# USBCharger.net
KiCad netlist of a schematic drawn in Altium Designer
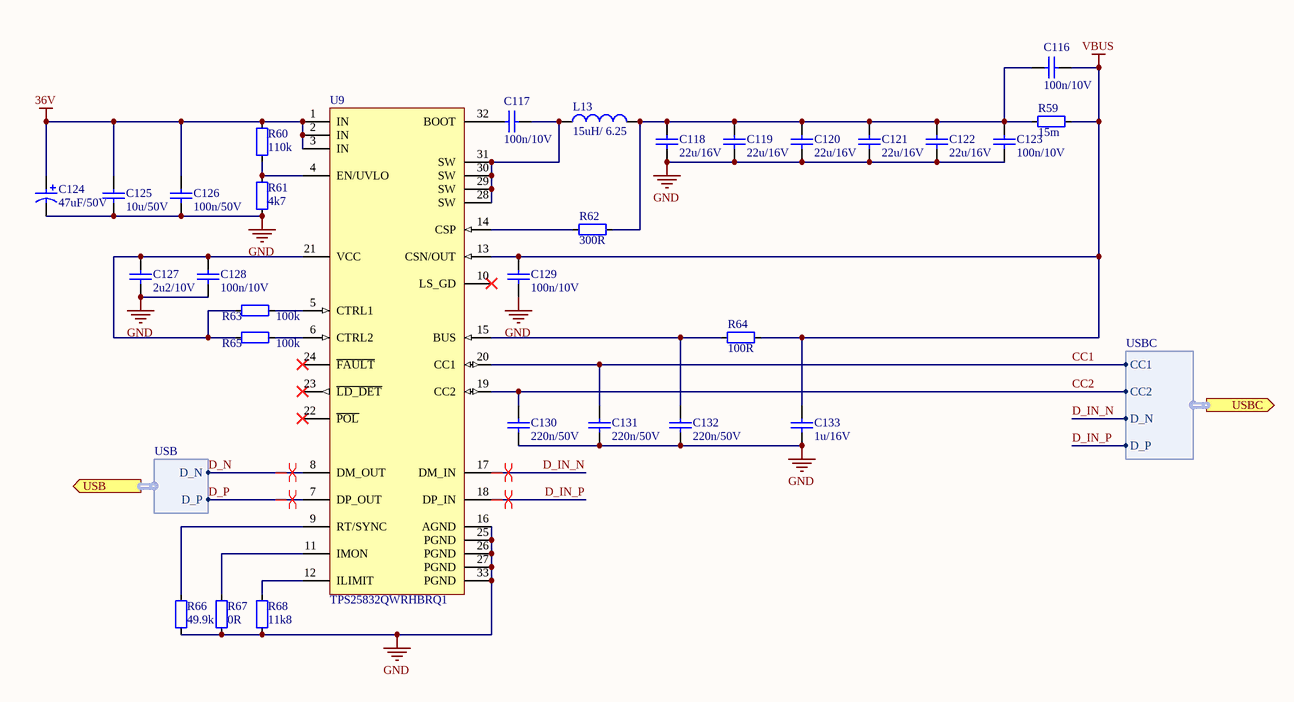
[diagram p0: USBCharger.SchDoc]

(export (version "E")
  (design (tool "Eeschema 10.0.6"))
  (components
    (comp (ref "C116")
      (value "100n/10V")
      (footprint "C0402")
      (fields (field (name "VOLTAGE") "10V") (field (name "TOLERANCE") "20%"))
      (libsource (lib "dk_capacitors") (part "100n 10V X5R 0402"))
    )
    (comp (ref "C117")
      (value "100n/10V")
      (footprint "C0402")
      (fields (field (name "VOLTAGE") "10V") (field (name "TOLERANCE") "20%"))
      (libsource (lib "dk_capacitors") (part "100n 10V X5R 0402"))
    )
    (comp (ref "C118")
      (value "22u/16V")
      (footprint "C1210")
      (fields (field (name "VOLTAGE") "16V") (field (name "TOLERANCE") "20%"))
      (libsource (lib "dk_capacitors") (part "22u 16V X7R 1210"))
    )
    (comp (ref "C119")
      (value "22u/16V")
      (footprint "C1210")
      (fields (field (name "VOLTAGE") "16V") (field (name "TOLERANCE") "20%"))
      (libsource (lib "dk_capacitors") (part "22u 16V X7R 1210"))
    )
    (comp (ref "C120")
      (value "22u/16V")
      (footprint "C1210")
      (fields (field (name "VOLTAGE") "16V") (field (name "TOLERANCE") "20%"))
      (libsource (lib "dk_capacitors") (part "22u 16V X7R 1210"))
    )
    (comp (ref "C121")
      (value "22u/16V")
      (footprint "C1210")
      (fields (field (name "VOLTAGE") "16V") (field (name "TOLERANCE") "20%"))
      (libsource (lib "dk_capacitors") (part "22u 16V X7R 1210"))
    )
    (comp (ref "C122")
      (value "22u/16V")
      (footprint "C1210")
      (fields (field (name "VOLTAGE") "16V") (field (name "TOLERANCE") "20%"))
      (libsource (lib "dk_capacitors") (part "22u 16V X7R 1210"))
    )
    (comp (ref "C123")
      (value "100n/10V")
      (footprint "C0402")
      (fields (field (name "VOLTAGE") "10V") (field (name "TOLERANCE") "20%"))
      (libsource (lib "dk_capacitors") (part "100n 10V X5R 0402"))
    )
    (comp (ref "C124")
      (value "47uF/50V")
      (footprint "WURTH-L6.5-D8")
      (description "Aluminium Electrolytic Capacitors - SMD WCAP-ASLI 50V 47uF 20% ESR=690mOhms")
      (fields (field (name "VOLTAGE") "50V") (field (name "TOLERANCE") "20%"))
      (libsource (lib "dk_electrolytic_caps") (part "Wurth-47uF-50V-L6.5-D8"))
    )
    (comp (ref "C125")
      (value "10u/50V")
      (footprint "C1210")
      (fields (field (name "VOLTAGE") "50V") (field (name "TOLERANCE") "10%"))
      (libsource (lib "dk_capacitors") (part "10u 50V X5R 1210"))
    )
    (comp (ref "C126")
      (value "100n/50V")
      (footprint "C0603")
      (fields (field (name "VOLTAGE") "50V") (field (name "TOLERANCE") "20%"))
      (libsource (lib "dk_capacitors") (part "100n 50V X7R 0603"))
    )
    (comp (ref "C127")
      (value "2u2/10V")
      (footprint "C0603")
      (fields (field (name "VOLTAGE") "10V") (field (name "TOLERANCE") "10%"))
      (libsource (lib "dk_capacitors") (part "2u2 10V X5R 0603"))
    )
    (comp (ref "C128")
      (value "100n/10V")
      (footprint "C0402")
      (fields (field (name "VOLTAGE") "10V") (field (name "TOLERANCE") "20%"))
      (libsource (lib "dk_capacitors") (part "100n 10V X5R 0402"))
    )
    (comp (ref "C129")
      (value "100n/10V")
      (footprint "C0402")
      (fields (field (name "VOLTAGE") "10V") (field (name "TOLERANCE") "20%"))
      (libsource (lib "dk_capacitors") (part "100n 10V X5R 0402"))
    )
    (comp (ref "C130")
      (value "220n/50V")
      (footprint "C0603")
      (fields (field (name "VOLTAGE") "50V") (field (name "TOLERANCE") "10%"))
      (libsource (lib "dk_capacitors") (part "220n 50V X7R 0603"))
    )
    (comp (ref "C131")
      (value "220n/50V")
      (footprint "C0603")
      (fields (field (name "VOLTAGE") "50V") (field (name "TOLERANCE") "10%"))
      (libsource (lib "dk_capacitors") (part "220n 50V X7R 0603"))
    )
    (comp (ref "C132")
      (value "220n/50V")
      (footprint "C0603")
      (fields (field (name "VOLTAGE") "50V") (field (name "TOLERANCE") "10%"))
      (libsource (lib "dk_capacitors") (part "220n 50V X7R 0603"))
    )
    (comp (ref "C133")
      (value "1u/16V")
      (footprint "C0603")
      (fields (field (name "VOLTAGE") "16V") (field (name "TOLERANCE") "10%"))
      (libsource (lib "dk_capacitors") (part "1u 16V X7R 0603"))
    )
    (comp (ref "L13")
      (value "15uH/ 6.25")
      (footprint "PA4342.XXXNLT")
      (description "Fixed Inductors 15uH 6.25A 4mm 20% Low Prof")
      (fields (field (name "TOLERANCE") "20%"))
      (libsource (lib "dk_inductors") (part "PA4342.153NLT"))
    )
    (comp (ref "R59")
      (value "15m")
      (footprint "R1206")
      (fields (field (name "TOLERANCE") "1%") (field (name "VOLTAGE") "100V"))
      (libsource (lib "dk_resistors") (part "15m 1W 100V 1206"))
    )
    (comp (ref "R60")
      (value "110k")
      (footprint "R0402")
      (fields (field (name "TOLERANCE") "1%") (field (name "VOLTAGE") "50V"))
      (libsource (lib "dk_resistors") (part "110k 63mW 50V 0402"))
    )
    (comp (ref "R61")
      (value "4k7")
      (footprint "R0402")
      (fields (field (name "TOLERANCE") "1%") (field (name "VOLTAGE") "50V"))
      (libsource (lib "dk_resistors") (part "4k7 63mW 50V 0402"))
    )
    (comp (ref "R62")
      (value "300R")
      (footprint "R0402")
      (fields (field (name "TOLERANCE") "1%") (field (name "VOLTAGE") "50V"))
      (libsource (lib "dk_resistors") (part "300R 63mW 50V 0402"))
    )
    (comp (ref "R63")
      (value "100k")
      (footprint "R0402")
      (fields (field (name "TOLERANCE") "1%") (field (name "VOLTAGE") "50V"))
      (libsource (lib "dk_resistors") (part "100k 63mW 50V 0402"))
    )
    (comp (ref "R64")
      (value "100R")
      (footprint "R0402")
      (fields (field (name "TOLERANCE") "1%") (field (name "VOLTAGE") "50V"))
      (libsource (lib "dk_resistors") (part "100R 63mW 50V 0402"))
    )
    (comp (ref "R65")
      (value "100k")
      (footprint "R0402")
      (fields (field (name "TOLERANCE") "1%") (field (name "VOLTAGE") "50V"))
      (libsource (lib "dk_resistors") (part "100k 63mW 50V 0402"))
    )
    (comp (ref "R66")
      (value "49.9k")
      (footprint "R0402")
      (fields (field (name "TOLERANCE") "1%") (field (name "VOLTAGE") "50V"))
      (libsource (lib "dk_resistors") (part "49k9 63mW 50V 0402"))
    )
    (comp (ref "R67")
      (value "0R")
      (footprint "R0402")
      (fields (field (name "TOLERANCE") "1%") (field (name "VOLTAGE") "50V"))
      (libsource (lib "dk_resistors") (part "0R 63mW 50V 0402"))
    )
    (comp (ref "R68")
      (value "11k8")
      (footprint "R0402")
      (fields (field (name "TOLERANCE") "1%") (field (name "VOLTAGE") "50V"))
      (libsource (lib "dk_resistors") (part "11k8 63mW 50V 0402"))
    )
    (comp (ref "U9")
      (value "TPS25832QWRHBRQ1")
      (footprint "VQFN-32")
      (libsource (lib "dk_ic_power") (part "TPS25832QWRHBRQ1"))
    )
  )
  (nets
    (net (code "3") (name "/CC1") (class "Default")
      (node (ref "C131") (pin "2") (pinfunction "2_2") (pintype "passive"))
      (node (ref "U9") (pin "20") (pinfunction "CC1_20") (pintype "bidirectional"))
    )
    (net (code "4") (name "/CC2") (class "Default")
      (node (ref "C130") (pin "2") (pinfunction "2_2") (pintype "passive"))
      (node (ref "U9") (pin "19") (pinfunction "CC2_19") (pintype "bidirectional"))
    )
    (net (code "5") (name "/D_IN_N") (class "Default")
      (node (ref "U9") (pin "17") (pinfunction "DM_IN_17") (pintype "passive"))
    )
    (net (code "6") (name "/D_IN_P") (class "Default")
      (node (ref "U9") (pin "18") (pinfunction "DP_IN_18") (pintype "passive"))
    )
    (net (code "7") (name "/D_N") (class "Default")
      (node (ref "U9") (pin "8") (pinfunction "DM_OUT_8") (pintype "passive"))
    )
    (net (code "8") (name "/D_P") (class "Default")
      (node (ref "U9") (pin "7") (pinfunction "DP_OUT_7") (pintype "passive"))
    )
    (net (code "11") (name "36V") (class "Default")
      (node (ref "C124") (pin "1") (pinfunction "1_1") (pintype "passive"))
      (node (ref "C125") (pin "2") (pinfunction "2_2") (pintype "passive"))
      (node (ref "C126") (pin "2") (pinfunction "2_2") (pintype "passive"))
      (node (ref "R60") (pin "2") (pinfunction "2_2") (pintype "passive"))
      (node (ref "U9") (pin "1") (pinfunction "IN_1") (pintype "power_in"))
      (node (ref "U9") (pin "2") (pinfunction "IN_2") (pintype "power_in"))
      (node (ref "U9") (pin "3") (pinfunction "IN_3") (pintype "power_in"))
    )
    (net (code "12") (name "GND") (class "Default")
      (node (ref "C118") (pin "1") (pinfunction "1_1") (pintype "passive"))
      (node (ref "C119") (pin "1") (pinfunction "1_1") (pintype "passive"))
      (node (ref "C120") (pin "1") (pinfunction "1_1") (pintype "passive"))
      (node (ref "C121") (pin "1") (pinfunction "1_1") (pintype "passive"))
      (node (ref "C122") (pin "1") (pinfunction "1_1") (pintype "passive"))
      (node (ref "C123") (pin "1") (pinfunction "1_1") (pintype "passive"))
      (node (ref "C124") (pin "2") (pinfunction "2_2") (pintype "passive"))
      (node (ref "C125") (pin "1") (pinfunction "1_1") (pintype "passive"))
      (node (ref "C126") (pin "1") (pinfunction "1_1") (pintype "passive"))
      (node (ref "C127") (pin "1") (pinfunction "1_1") (pintype "passive"))
      (node (ref "C128") (pin "1") (pinfunction "1_1") (pintype "passive"))
      (node (ref "C129") (pin "1") (pinfunction "1_1") (pintype "passive"))
      (node (ref "C130") (pin "1") (pinfunction "1_1") (pintype "passive"))
      (node (ref "C131") (pin "1") (pinfunction "1_1") (pintype "passive"))
      (node (ref "C132") (pin "1") (pinfunction "1_1") (pintype "passive"))
      (node (ref "C133") (pin "1") (pinfunction "1_1") (pintype "passive"))
      (node (ref "R61") (pin "1") (pinfunction "1_1") (pintype "passive"))
      (node (ref "R66") (pin "1") (pinfunction "1_1") (pintype "passive"))
      (node (ref "R67") (pin "1") (pinfunction "1_1") (pintype "passive"))
      (node (ref "R68") (pin "1") (pinfunction "1_1") (pintype "passive"))
      (node (ref "U9") (pin "16") (pinfunction "AGND_16") (pintype "power_in"))
      (node (ref "U9") (pin "25") (pinfunction "PGND_25") (pintype "power_in"))
      (node (ref "U9") (pin "26") (pinfunction "PGND_26") (pintype "power_in"))
      (node (ref "U9") (pin "27") (pinfunction "PGND_27") (pintype "power_in"))
      (node (ref "U9") (pin "33") (pinfunction "PGND_33") (pintype "power_in"))
    )
    (net (code "13") (name "Net-(C116-Pad1)") (class "Default")
      (node (ref "C116") (pin "1") (pinfunction "1_1") (pintype "passive"))
      (node (ref "C118") (pin "2") (pinfunction "2_2") (pintype "passive"))
      (node (ref "C119") (pin "2") (pinfunction "2_2") (pintype "passive"))
      (node (ref "C120") (pin "2") (pinfunction "2_2") (pintype "passive"))
      (node (ref "C121") (pin "2") (pinfunction "2_2") (pintype "passive"))
      (node (ref "C122") (pin "2") (pinfunction "2_2") (pintype "passive"))
      (node (ref "C123") (pin "2") (pinfunction "2_2") (pintype "passive"))
      (node (ref "L13") (pin "2") (pinfunction "2_2") (pintype "passive"))
      (node (ref "R59") (pin "1") (pinfunction "1_1") (pintype "passive"))
      (node (ref "R62") (pin "2") (pinfunction "2_2") (pintype "passive"))
    )
    (net (code "14") (name "Net-(C117-Pad2)") (class "Default")
      (node (ref "C117") (pin "2") (pinfunction "2_2") (pintype "passive"))
      (node (ref "L13") (pin "1") (pinfunction "1_1") (pintype "passive"))
      (node (ref "U9") (pin "28") (pinfunction "SW_28") (pintype "power_in"))
      (node (ref "U9") (pin "29") (pinfunction "SW_29") (pintype "power_in"))
      (node (ref "U9") (pin "30") (pinfunction "SW_30") (pintype "power_in"))
      (node (ref "U9") (pin "31") (pinfunction "SW_31") (pintype "power_in"))
    )
    (net (code "15") (name "Net-(U9-BOOT)") (class "Default")
      (node (ref "C117") (pin "1") (pinfunction "1_1") (pintype "passive"))
      (node (ref "U9") (pin "32") (pinfunction "BOOT_32") (pintype "power_in"))
    )
    (net (code "16") (name "Net-(U9-BUS)") (class "Default")
      (node (ref "C132") (pin "2") (pinfunction "2_2") (pintype "passive"))
      (node (ref "R64") (pin "1") (pinfunction "1_1") (pintype "passive"))
      (node (ref "U9") (pin "15") (pinfunction "BUS_15") (pintype "input"))
    )
    (net (code "17") (name "Net-(U9-CSP)") (class "Default")
      (node (ref "R62") (pin "1") (pinfunction "1_1") (pintype "passive"))
      (node (ref "U9") (pin "14") (pinfunction "CSP_14") (pintype "input"))
    )
    (net (code "18") (name "Net-(U9-CTRL1)") (class "Default")
      (node (ref "R63") (pin "2") (pinfunction "2_2") (pintype "passive"))
      (node (ref "U9") (pin "5") (pinfunction "CTRL1_5") (pintype "input"))
    )
    (net (code "19") (name "Net-(U9-CTRL2)") (class "Default")
      (node (ref "R65") (pin "2") (pinfunction "2_2") (pintype "passive"))
      (node (ref "U9") (pin "6") (pinfunction "CTRL2_6") (pintype "input"))
    )
    (net (code "20") (name "Net-(U9-EN{slash}UVLO)") (class "Default")
      (node (ref "R60") (pin "1") (pinfunction "1_1") (pintype "passive"))
      (node (ref "R61") (pin "2") (pinfunction "2_2") (pintype "passive"))
      (node (ref "U9") (pin "4") (pinfunction "EN/UVLO_4") (pintype "passive"))
    )
    (net (code "21") (name "Net-(U9-ILIMIT)") (class "Default")
      (node (ref "R68") (pin "2") (pinfunction "2_2") (pintype "passive"))
      (node (ref "U9") (pin "12") (pinfunction "ILIMIT_12") (pintype "passive"))
    )
    (net (code "22") (name "Net-(U9-IMON)") (class "Default")
      (node (ref "R67") (pin "2") (pinfunction "2_2") (pintype "passive"))
      (node (ref "U9") (pin "11") (pinfunction "IMON_11") (pintype "passive"))
    )
    (net (code "23") (name "Net-(U9-RT{slash}SYNC)") (class "Default")
      (node (ref "R66") (pin "2") (pinfunction "2_2") (pintype "passive"))
      (node (ref "U9") (pin "9") (pinfunction "RT/SYNC_9") (pintype "passive"))
    )
    (net (code "24") (name "Net-(U9-VCC)") (class "Default")
      (node (ref "C127") (pin "2") (pinfunction "2_2") (pintype "passive"))
      (node (ref "C128") (pin "2") (pinfunction "2_2") (pintype "passive"))
      (node (ref "R63") (pin "1") (pinfunction "1_1") (pintype "passive"))
      (node (ref "R65") (pin "1") (pinfunction "1_1") (pintype "passive"))
      (node (ref "U9") (pin "21") (pinfunction "VCC_21") (pintype "power_in"))
    )
    (net (code "25") (name "VBUS") (class "Default")
      (node (ref "C116") (pin "2") (pinfunction "2_2") (pintype "passive"))
      (node (ref "C129") (pin "2") (pinfunction "2_2") (pintype "passive"))
      (node (ref "C133") (pin "2") (pinfunction "2_2") (pintype "passive"))
      (node (ref "R59") (pin "2") (pinfunction "2_2") (pintype "passive"))
      (node (ref "R64") (pin "2") (pinfunction "2_2") (pintype "passive"))
      (node (ref "U9") (pin "13") (pinfunction "CSN/OUT_13") (pintype "input"))
    )
    (net (code "26") (name "unconnected-(U9-LS_GD-Pad10)") (class "Default")
      (node (ref "U9") (pin "10") (pinfunction "LS_GD_10") (pintype "passive+no_connect"))
    )
    (net (code "27") (name "unconnected-(U9-~{FAULT}-Pad24)") (class "Default")
      (node (ref "U9") (pin "24") (pinfunction "~{FAULT}_24") (pintype "open_collector+no_connect"))
    )
    (net (code "28") (name "unconnected-(U9-~{LD_DET}-Pad23)") (class "Default")
      (node (ref "U9") (pin "23") (pinfunction "~{LD_DET}_23") (pintype "output+no_connect"))
    )
    (net (code "29") (name "unconnected-(U9-~{POL}-Pad22)") (class "Default")
      (node (ref "U9") (pin "22") (pinfunction "~{POL}_22") (pintype "open_collector+no_connect"))
    )
  )
)
